# pot.net
KiCad netlist of a schematic drawn in EAGLE
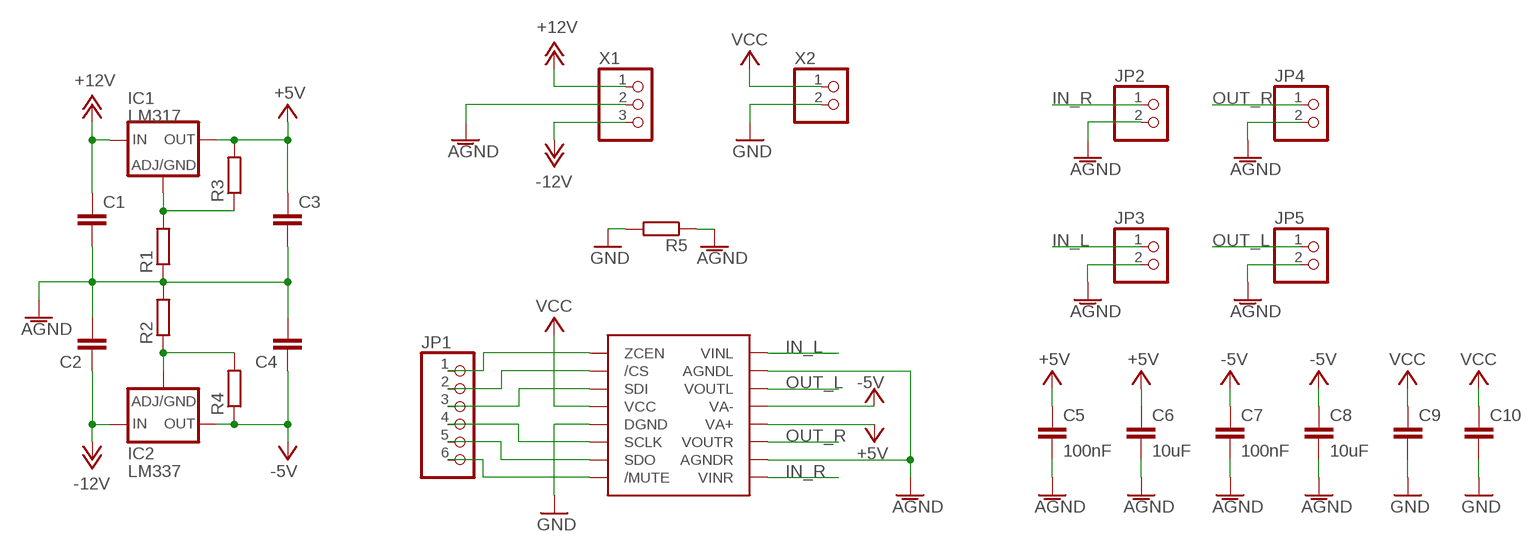
[diagram p0: schematic, sheet 1]

(export (version "E")
  (design (tool "Eeschema 10.0.6"))
  (components
    (comp (ref "C1")
      (value "C-EUC0805K")
      (footprint "eagle-import:C0805K")
      (libsource (lib "eagle-import") (part "C-EUC0805K"))
    )
    (comp (ref "C2")
      (value "C-EUC0805K")
      (footprint "eagle-import:C0805K")
      (libsource (lib "eagle-import") (part "C-EUC0805K"))
    )
    (comp (ref "C3")
      (value "C-EUC0805K")
      (footprint "eagle-import:C0805K")
      (libsource (lib "eagle-import") (part "C-EUC0805K"))
    )
    (comp (ref "C4")
      (value "C-EUC0805K")
      (footprint "eagle-import:C0805K")
      (libsource (lib "eagle-import") (part "C-EUC0805K"))
    )
    (comp (ref "C5")
      (value "100nF")
      (footprint "eagle-import:C0805K")
      (libsource (lib "eagle-import") (part "C-EUC0805K"))
    )
    (comp (ref "C6")
      (value "10uF")
      (footprint "eagle-import:C0805K")
      (libsource (lib "eagle-import") (part "C-EUC0805K"))
    )
    (comp (ref "C7")
      (value "100nF")
      (footprint "eagle-import:C0805K")
      (libsource (lib "eagle-import") (part "C-EUC0805K"))
    )
    (comp (ref "C8")
      (value "10uF")
      (footprint "eagle-import:C0805K")
      (libsource (lib "eagle-import") (part "C-EUC0805K"))
    )
    (comp (ref "C9")
      (value "C-EUC0805K")
      (footprint "eagle-import:C0805K")
      (libsource (lib "eagle-import") (part "C-EUC0805K"))
    )
    (comp (ref "C10")
      (value "C-EUC0805K")
      (footprint "eagle-import:C0805K")
      (libsource (lib "eagle-import") (part "C-EUC0805K"))
    )
    (comp (ref "IC1")
      (value "LM317")
      (footprint "eagle-import:SOT223")
      (libsource (lib "eagle-import") (part "LM317"))
    )
    (comp (ref "IC2")
      (value "LM337")
      (footprint "eagle-import:SOT223")
      (libsource (lib "eagle-import") (part "LM337"))
    )
    (comp (ref "JP1")
      (value "PINHD-1X6")
      (footprint "eagle-import:1X06")
      (libsource (lib "eagle-import") (part "PINHD-1X6"))
    )
    (comp (ref "JP2")
      (value "PINHD-1X2")
      (footprint "eagle-import:1X02")
      (libsource (lib "eagle-import") (part "PINHD-1X2"))
    )
    (comp (ref "JP3")
      (value "PINHD-1X2")
      (footprint "eagle-import:1X02")
      (libsource (lib "eagle-import") (part "PINHD-1X2"))
    )
    (comp (ref "JP4")
      (value "PINHD-1X2")
      (footprint "eagle-import:1X02")
      (libsource (lib "eagle-import") (part "PINHD-1X2"))
    )
    (comp (ref "JP5")
      (value "PINHD-1X2")
      (footprint "eagle-import:1X02")
      (libsource (lib "eagle-import") (part "PINHD-1X2"))
    )
    (comp (ref "R1")
      (value "R-EU_")
      (footprint "eagle-import:R0805")
      (libsource (lib "eagle-import") (part "R-EU_"))
    )
    (comp (ref "R2")
      (value "R-EU_")
      (footprint "eagle-import:R0805")
      (libsource (lib "eagle-import") (part "R-EU_"))
    )
    (comp (ref "R3")
      (value "R-EU_")
      (footprint "eagle-import:R0805")
      (libsource (lib "eagle-import") (part "R-EU_"))
    )
    (comp (ref "R4")
      (value "R-EU_")
      (footprint "eagle-import:R0805")
      (libsource (lib "eagle-import") (part "R-EU_"))
    )
    (comp (ref "R5")
      (value "R-EU_")
      (footprint "eagle-import:R0805")
      (libsource (lib "eagle-import") (part "R-EU_"))
    )
    (comp (ref "U1")
      (value "PGA2311")
      (footprint "eagle-import:SO16W")
      (libsource (lib "eagle-import") (part "PGA2311"))
    )
    (comp (ref "X1")
      (value "22-23-2031")
      (footprint "eagle-import:22-23-2031")
      (libsource (lib "eagle-import") (part "22-23-2031"))
    )
    (comp (ref "X2")
      (value "22-23-2021")
      (footprint "eagle-import:22-23-2021")
      (libsource (lib "eagle-import") (part "22-23-2021"))
    )
  )
  (nets
    (net (code "1") (name "+5V") (class "Default")
      (node (ref "C3") (pin "1") (pinfunction "1_1") (pintype "passive"))
      (node (ref "C5") (pin "1") (pinfunction "1_1") (pintype "passive"))
      (node (ref "C6") (pin "1") (pinfunction "1_1") (pintype "passive"))
      (node (ref "IC1") (pin "2") (pinfunction "OUT_2") (pintype "passive"))
      (node (ref "IC1") (pin "4") (pinfunction "OUT_4") (pintype "passive"))
      (node (ref "R3") (pin "2") (pinfunction "2_2") (pintype "passive"))
      (node (ref "U1") (pin "12") (pinfunction "VA+_12") (pintype "bidirectional"))
    )
    (net (code "2") (name "+12V") (class "Default")
      (node (ref "C1") (pin "1") (pinfunction "1_1") (pintype "passive"))
      (node (ref "IC1") (pin "3") (pinfunction "IN_3") (pintype "input"))
      (node (ref "X1") (pin "1") (pinfunction "1_1") (pintype "passive"))
    )
    (net (code "3") (name "-5V") (class "Default")
      (node (ref "C4") (pin "1") (pinfunction "1_1") (pintype "passive"))
      (node (ref "C7") (pin "1") (pinfunction "1_1") (pintype "passive"))
      (node (ref "C8") (pin "1") (pinfunction "1_1") (pintype "passive"))
      (node (ref "IC2") (pin "3") (pinfunction "OUT_3") (pintype "passive"))
      (node (ref "R4") (pin "1") (pinfunction "1_1") (pintype "passive"))
      (node (ref "U1") (pin "13") (pinfunction "VA-_13") (pintype "bidirectional"))
    )
    (net (code "4") (name "-12V") (class "Default")
      (node (ref "C2") (pin "1") (pinfunction "1_1") (pintype "passive"))
      (node (ref "IC2") (pin "2") (pinfunction "IN_2") (pintype "input"))
      (node (ref "IC2") (pin "4") (pinfunction "IN_4") (pintype "input"))
      (node (ref "X1") (pin "3") (pinfunction "3_3") (pintype "passive"))
    )
    (net (code "5") (name "/IN_L") (class "Default")
      (node (ref "JP3") (pin "1") (pinfunction "1_1") (pintype "passive"))
      (node (ref "U1") (pin "16") (pinfunction "VINL_16") (pintype "bidirectional"))
    )
    (net (code "6") (name "/IN_R") (class "Default")
      (node (ref "JP2") (pin "1") (pinfunction "1_1") (pintype "passive"))
      (node (ref "U1") (pin "9") (pinfunction "VINR_9") (pintype "bidirectional"))
    )
    (net (code "7") (name "/OUT_L") (class "Default")
      (node (ref "JP5") (pin "1") (pinfunction "1_1") (pintype "passive"))
      (node (ref "U1") (pin "14") (pinfunction "VOUTL_14") (pintype "bidirectional"))
    )
    (net (code "8") (name "/OUT_R") (class "Default")
      (node (ref "JP4") (pin "1") (pinfunction "1_1") (pintype "passive"))
      (node (ref "U1") (pin "11") (pinfunction "VOUTR_11") (pintype "bidirectional"))
    )
    (net (code "9") (name "AGND") (class "Default")
      (node (ref "C1") (pin "2") (pinfunction "2_2") (pintype "passive"))
      (node (ref "C2") (pin "2") (pinfunction "2_2") (pintype "passive"))
      (node (ref "C3") (pin "2") (pinfunction "2_2") (pintype "passive"))
      (node (ref "C4") (pin "2") (pinfunction "2_2") (pintype "passive"))
      (node (ref "C5") (pin "2") (pinfunction "2_2") (pintype "passive"))
      (node (ref "C6") (pin "2") (pinfunction "2_2") (pintype "passive"))
      (node (ref "C7") (pin "2") (pinfunction "2_2") (pintype "passive"))
      (node (ref "C8") (pin "2") (pinfunction "2_2") (pintype "passive"))
      (node (ref "JP2") (pin "2") (pinfunction "2_2") (pintype "passive"))
      (node (ref "JP3") (pin "2") (pinfunction "2_2") (pintype "passive"))
      (node (ref "JP4") (pin "2") (pinfunction "2_2") (pintype "passive"))
      (node (ref "JP5") (pin "2") (pinfunction "2_2") (pintype "passive"))
      (node (ref "R1") (pin "1") (pinfunction "1_1") (pintype "passive"))
      (node (ref "R2") (pin "2") (pinfunction "2_2") (pintype "passive"))
      (node (ref "R5") (pin "1") (pinfunction "1_1") (pintype "passive"))
      (node (ref "U1") (pin "10") (pinfunction "AGNDR_10") (pintype "bidirectional"))
      (node (ref "U1") (pin "15") (pinfunction "AGNDL_15") (pintype "bidirectional"))
      (node (ref "X1") (pin "2") (pinfunction "2_2") (pintype "passive"))
    )
    (net (code "10") (name "GND") (class "Default")
      (node (ref "C10") (pin "2") (pinfunction "2_2") (pintype "passive"))
      (node (ref "C9") (pin "2") (pinfunction "2_2") (pintype "passive"))
      (node (ref "R5") (pin "2") (pinfunction "2_2") (pintype "passive"))
      (node (ref "U1") (pin "5") (pinfunction "DGND_5") (pintype "bidirectional"))
      (node (ref "X2") (pin "2") (pinfunction "2_2") (pintype "passive"))
    )
    (net (code "11") (name "Net-(IC1-ADJ)") (class "Default")
      (node (ref "IC1") (pin "1") (pinfunction "ADJ_1") (pintype "input"))
      (node (ref "R1") (pin "2") (pinfunction "2_2") (pintype "passive"))
      (node (ref "R3") (pin "1") (pinfunction "1_1") (pintype "passive"))
    )
    (net (code "12") (name "Net-(IC2-ADJ)") (class "Default")
      (node (ref "IC2") (pin "1") (pinfunction "ADJ_1") (pintype "input"))
      (node (ref "R2") (pin "1") (pinfunction "1_1") (pintype "passive"))
      (node (ref "R4") (pin "2") (pinfunction "2_2") (pintype "passive"))
    )
    (net (code "13") (name "Net-(U1-SCLK)") (class "Default")
      (node (ref "JP1") (pin "4") (pinfunction "4_4") (pintype "passive"))
      (node (ref "U1") (pin "6") (pinfunction "SCLK_6") (pintype "bidirectional"))
    )
    (net (code "14") (name "Net-(U1-SDI)") (class "Default")
      (node (ref "JP1") (pin "3") (pinfunction "3_3") (pintype "passive"))
      (node (ref "U1") (pin "3") (pinfunction "SDI_3") (pintype "bidirectional"))
    )
    (net (code "15") (name "Net-(U1-SDO)") (class "Default")
      (node (ref "JP1") (pin "5") (pinfunction "5_5") (pintype "passive"))
      (node (ref "U1") (pin "7") (pinfunction "SDO_7") (pintype "bidirectional"))
    )
    (net (code "16") (name "Net-(U1-ZCEN)") (class "Default")
      (node (ref "JP1") (pin "1") (pinfunction "1_1") (pintype "passive"))
      (node (ref "U1") (pin "1") (pinfunction "ZCEN_1") (pintype "bidirectional"))
    )
    (net (code "17") (name "Net-(U1-{slash}CS)") (class "Default")
      (node (ref "JP1") (pin "2") (pinfunction "2_2") (pintype "passive"))
      (node (ref "U1") (pin "2") (pinfunction "/CS_2") (pintype "bidirectional"))
    )
    (net (code "18") (name "Net-(U1-{slash}MUTE)") (class "Default")
      (node (ref "JP1") (pin "6") (pinfunction "6_6") (pintype "passive"))
      (node (ref "U1") (pin "8") (pinfunction "/MUTE_8") (pintype "bidirectional"))
    )
    (net (code "19") (name "VCC") (class "Default")
      (node (ref "C10") (pin "1") (pinfunction "1_1") (pintype "passive"))
      (node (ref "C9") (pin "1") (pinfunction "1_1") (pintype "passive"))
      (node (ref "U1") (pin "4") (pinfunction "VCC_4") (pintype "bidirectional"))
      (node (ref "X2") (pin "1") (pinfunction "1_1") (pintype "passive"))
    )
  )
)
